# Grove_-_3-Axis_Digital_Accelerometer_400.net
KiCad netlist of a schematic drawn in EAGLE
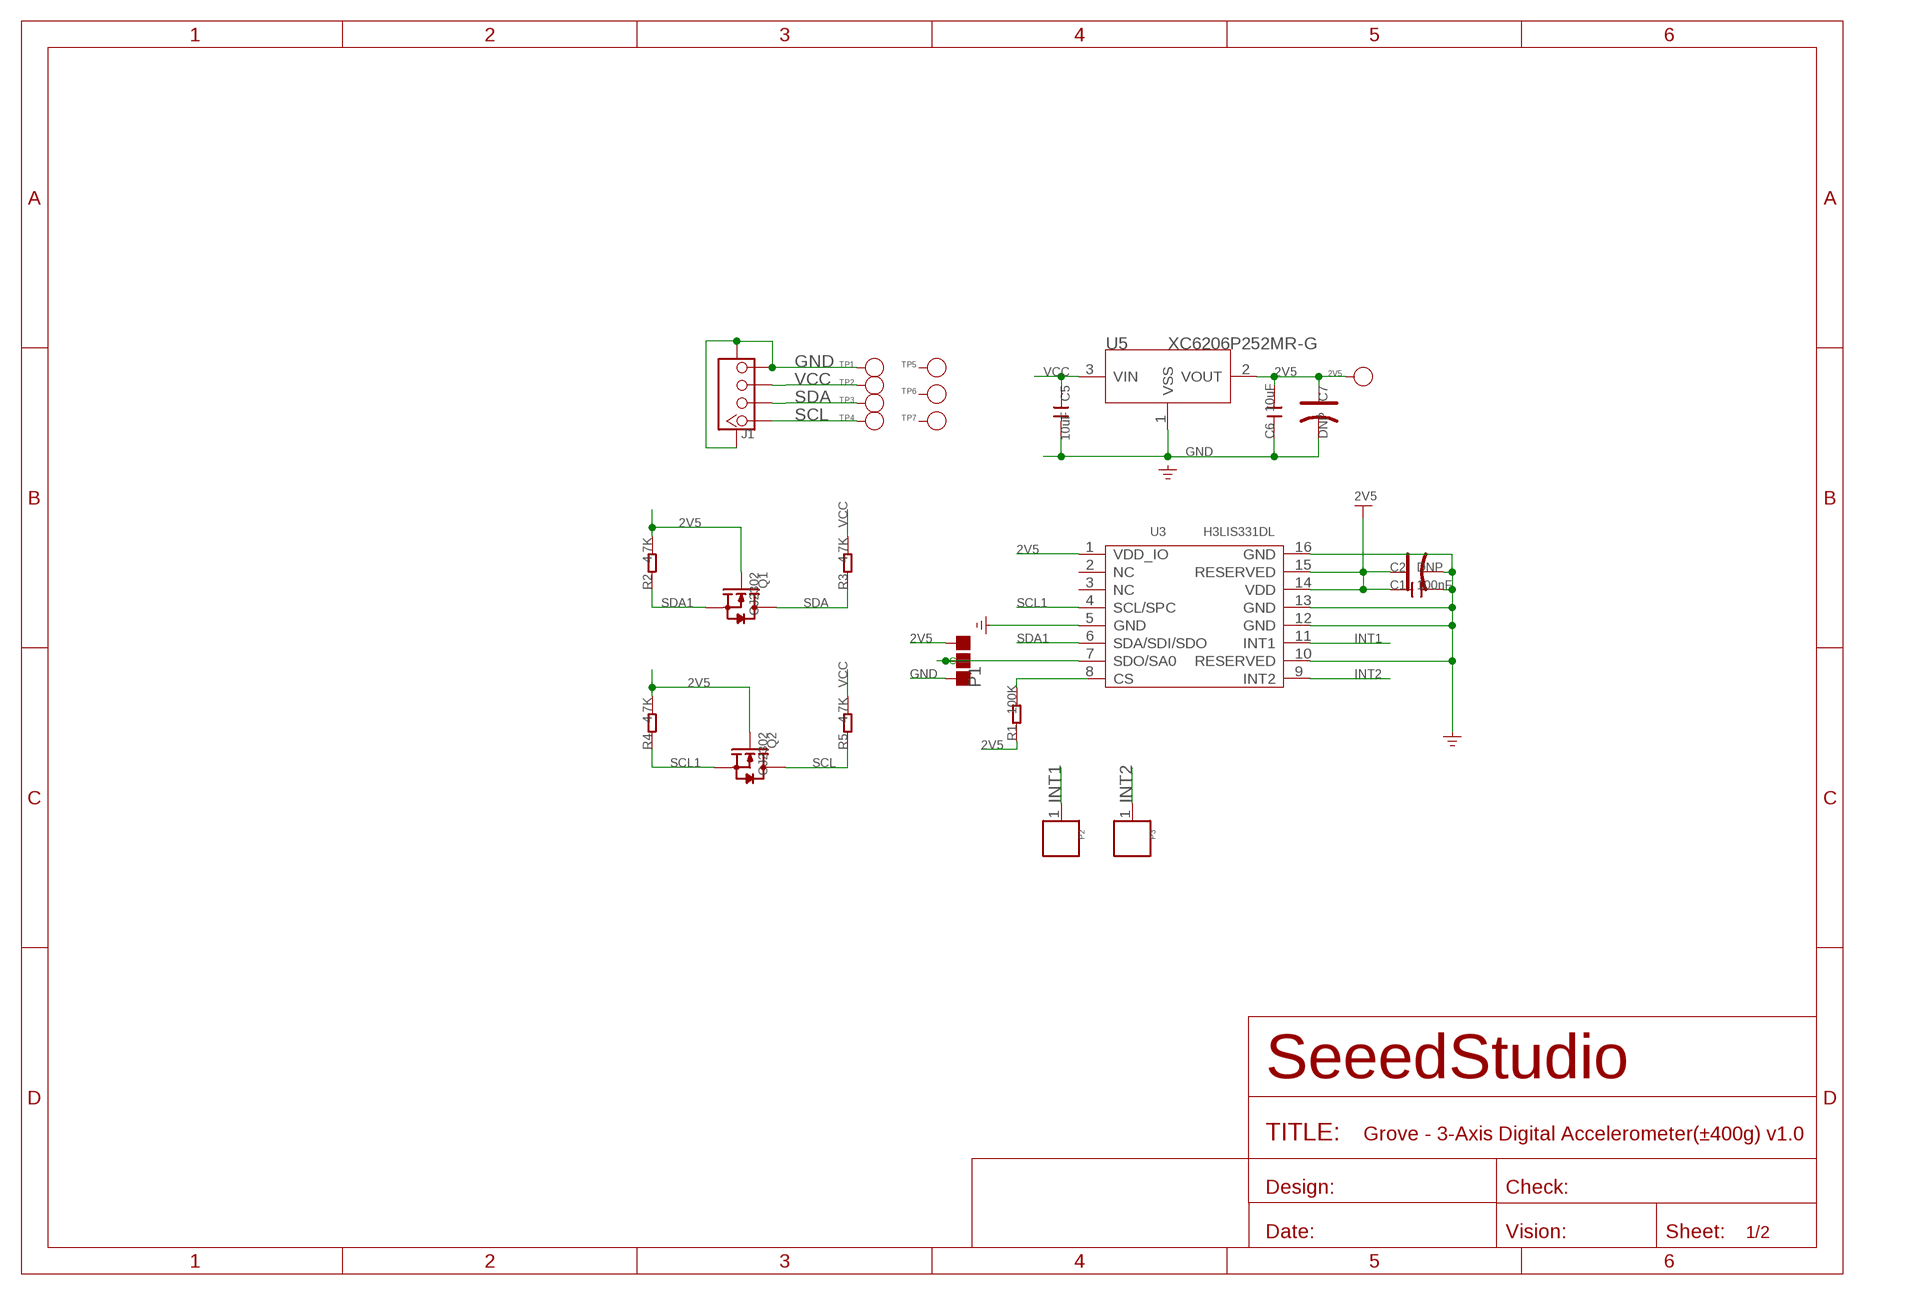
[diagram p0: schematic, sheet 1]
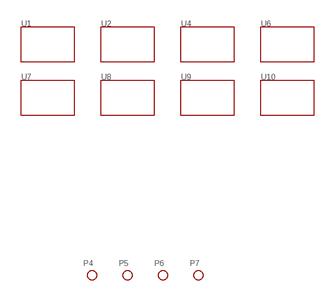
[diagram p1: schematic, sheet 2]

(export (version "E")
  (design (tool "Eeschema 10.0.6"))
  (components
    (comp (ref "2V5")
      (value "PAD-TEST-POINT'4545'")
      (footprint "eagle-import:TP_4545")
      (fields (field (name "PARTNO") "DNP"))
      (libsource (lib "eagle-import") (part "PAD-TEST-POINT'4545'"))
    )
    (comp (ref "C1")
      (value "100nF")
      (footprint "eagle-import:C0603")
      (libsource (lib "eagle-import") (part "C-0603"))
    )
    (comp (ref "C2")
      (value "DNP")
      (footprint "eagle-import:AVX-A")
      (libsource (lib "eagle-import") (part "CAP-AVX-A"))
    )
    (comp (ref "C5")
      (value "10uF")
      (footprint "eagle-import:C0805")
      (libsource (lib "eagle-import") (part "C-0805"))
    )
    (comp (ref "C6")
      (value "10uF")
      (footprint "eagle-import:C0805")
      (libsource (lib "eagle-import") (part "C-0805"))
    )
    (comp (ref "C7")
      (value "DNP")
      (footprint "eagle-import:AVX-A")
      (libsource (lib "eagle-import") (part "CAP-AVX-A"))
    )
    (comp (ref "J1")
      (value "TWIG-4P-2.0-SMD-FEMALE-REINFORCE'DD'")
      (footprint "eagle-import:4P-SMD-2.0")
      (libsource (lib "eagle-import") (part "TWIG-4P-2.0-SMD-FEMALE-REINFORCE'DD'"))
    )
    (comp (ref "P1")
      (value "PAD-JUMPER-3P-40*40")
      (footprint "eagle-import:3P-SMD-4.1X1.5")
      (fields (field (name "PARTNO") "DNP"))
      (libsource (lib "eagle-import") (part "PAD-JUMPER-3P-4040"))
    )
    (comp (ref "P2")
      (value "PAD'60/30'")
      (footprint "eagle-import:1P-65_35MIL")
      (libsource (lib "eagle-import") (part "PAD'60/30'"))
    )
    (comp (ref "P3")
      (value "PAD'60/30'")
      (footprint "eagle-import:1P-65_35MIL")
      (libsource (lib "eagle-import") (part "PAD'60/30'"))
    )
    (comp (ref "Q1")
      (value "CJ2302")
      (footprint "eagle-import:SOT23")
      (libsource (lib "eagle-import") (part "MOSFET-N'SOT23'"))
    )
    (comp (ref "Q2")
      (value "CJ2302")
      (footprint "eagle-import:SOT23")
      (libsource (lib "eagle-import") (part "MOSFET-N'SOT23'"))
    )
    (comp (ref "R1")
      (value "100K")
      (footprint "eagle-import:R0603")
      (libsource (lib "eagle-import") (part "R-0603"))
    )
    (comp (ref "R2")
      (value "4.7K")
      (footprint "eagle-import:R0603")
      (libsource (lib "eagle-import") (part "R-0603"))
    )
    (comp (ref "R3")
      (value "4.7K")
      (footprint "eagle-import:R0603")
      (libsource (lib "eagle-import") (part "R-0603"))
    )
    (comp (ref "R4")
      (value "4.7K")
      (footprint "eagle-import:R0603")
      (libsource (lib "eagle-import") (part "R-0603"))
    )
    (comp (ref "R5")
      (value "4.7K")
      (footprint "eagle-import:R0603")
      (libsource (lib "eagle-import") (part "R-0603"))
    )
    (comp (ref "TP1")
      (value "PAD-TEST-POINT'4545'")
      (footprint "eagle-import:TP_4545")
      (fields (field (name "PARTNO") "DNP"))
      (libsource (lib "eagle-import") (part "PAD-TEST-POINT'4545'"))
    )
    (comp (ref "TP2")
      (value "PAD-TEST-POINT'4545'")
      (footprint "eagle-import:TP_4545")
      (fields (field (name "PARTNO") "DNP"))
      (libsource (lib "eagle-import") (part "PAD-TEST-POINT'4545'"))
    )
    (comp (ref "TP3")
      (value "PAD-TEST-POINT'4545'")
      (footprint "eagle-import:TP_4545")
      (fields (field (name "PARTNO") "DNP"))
      (libsource (lib "eagle-import") (part "PAD-TEST-POINT'4545'"))
    )
    (comp (ref "TP4")
      (value "PAD-TEST-POINT'4545'")
      (footprint "eagle-import:TP_4545")
      (fields (field (name "PARTNO") "DNP"))
      (libsource (lib "eagle-import") (part "PAD-TEST-POINT'4545'"))
    )
    (comp (ref "TP5")
      (value "PAD-TEST-POINT'4545'")
      (footprint "eagle-import:TP_4545")
      (fields (field (name "PARTNO") "DNP"))
      (libsource (lib "eagle-import") (part "PAD-TEST-POINT'4545'"))
    )
    (comp (ref "TP6")
      (value "PAD-TEST-POINT'4545'")
      (footprint "eagle-import:TP_4545")
      (fields (field (name "PARTNO") "DNP"))
      (libsource (lib "eagle-import") (part "PAD-TEST-POINT'4545'"))
    )
    (comp (ref "TP7")
      (value "PAD-TEST-POINT'4545'")
      (footprint "eagle-import:TP_4545")
      (fields (field (name "PARTNO") "DNP"))
      (libsource (lib "eagle-import") (part "PAD-TEST-POINT'4545'"))
    )
    (comp (ref "U3")
      (value "H3LIS331DL")
      (footprint "eagle-import:TFLGA-16")
      (libsource (lib "eagle-import") (part "H3LIS331DL"))
    )
    (comp (ref "U5")
      (value "XC6206P252MR-G")
      (footprint "eagle-import:SOT23")
      (libsource (lib "eagle-import") (part "XC6206MR"))
    )
    (comp (ref "P4")
      (value "PAD-MARK")
      (footprint "eagle-import:ROUND-MARK-1.0")
      (fields (field (name "PARTNO") "DNP"))
      (libsource (lib "eagle-import") (part "PAD-MARK"))
    )
    (comp (ref "P5")
      (value "PAD-MARK")
      (footprint "eagle-import:ROUND-MARK-1.0")
      (fields (field (name "PARTNO") "DNP"))
      (libsource (lib "eagle-import") (part "PAD-MARK"))
    )
    (comp (ref "P6")
      (value "PAD-MARK")
      (footprint "eagle-import:ROUND-MARK-1.0")
      (fields (field (name "PARTNO") "DNP"))
      (libsource (lib "eagle-import") (part "PAD-MARK"))
    )
    (comp (ref "P7")
      (value "PAD-MARK")
      (footprint "eagle-import:ROUND-MARK-1.0")
      (fields (field (name "PARTNO") "DNP"))
      (libsource (lib "eagle-import") (part "PAD-MARK"))
    )
    (comp (ref "U1")
      (value "TWIG'2U'")
      (footprint "eagle-import:GROVE-TEST-PLATFORM")
      (libsource (lib "eagle-import") (part "TWIG'2U'"))
    )
    (comp (ref "U2")
      (value "TWIG'2U'")
      (footprint "eagle-import:GROVE-TEST-PLATFORM")
      (libsource (lib "eagle-import") (part "TWIG'2U'"))
    )
    (comp (ref "U4")
      (value "TWIG'2U'")
      (footprint "eagle-import:GROVE-TEST-PLATFORM")
      (libsource (lib "eagle-import") (part "TWIG'2U'"))
    )
    (comp (ref "U6")
      (value "TWIG'2U'")
      (footprint "eagle-import:GROVE-TEST-PLATFORM")
      (libsource (lib "eagle-import") (part "TWIG'2U'"))
    )
    (comp (ref "U7")
      (value "TWIG'2U'")
      (footprint "eagle-import:GROVE-TEST-PLATFORM")
      (libsource (lib "eagle-import") (part "TWIG'2U'"))
    )
    (comp (ref "U8")
      (value "TWIG'2U'")
      (footprint "eagle-import:GROVE-TEST-PLATFORM")
      (libsource (lib "eagle-import") (part "TWIG'2U'"))
    )
    (comp (ref "U9")
      (value "TWIG'2U'")
      (footprint "eagle-import:GROVE-TEST-PLATFORM")
      (libsource (lib "eagle-import") (part "TWIG'2U'"))
    )
    (comp (ref "U10")
      (value "TWIG'2U'")
      (footprint "eagle-import:GROVE-TEST-PLATFORM")
      (libsource (lib "eagle-import") (part "TWIG'2U'"))
    )
  )
  (nets
    (net (code "1") (name "2V5") (class "Default")
      (node (ref "2V5") (pin "T") (pinfunction "T_T") (pintype "bidirectional"))
      (node (ref "C1") (pin "1") (pinfunction "1_1") (pintype "passive"))
      (node (ref "C2") (pin "+") (pinfunction "+_+") (pintype "passive"))
      (node (ref "C6") (pin "2") (pinfunction "2_2") (pintype "passive"))
      (node (ref "C7") (pin "+") (pinfunction "+_+") (pintype "passive"))
      (node (ref "P1") (pin "00") (pinfunction "L_00") (pintype "bidirectional"))
      (node (ref "Q1") (pin "1") (pinfunction "G_1") (pintype "passive"))
      (node (ref "Q2") (pin "1") (pinfunction "G_1") (pintype "passive"))
      (node (ref "R1") (pin "1") (pinfunction "1_1") (pintype "passive"))
      (node (ref "R2") (pin "2") (pinfunction "2_2") (pintype "passive"))
      (node (ref "R4") (pin "2") (pinfunction "2_2") (pintype "passive"))
      (node (ref "U3") (pin "1") (pinfunction "VDD_IO_1") (pintype "bidirectional"))
      (node (ref "U3") (pin "14") (pinfunction "VDD_14") (pintype "bidirectional"))
      (node (ref "U3") (pin "15") (pinfunction "RESERVED_15") (pintype "bidirectional"))
      (node (ref "U5") (pin "2") (pinfunction "VOUT_2") (pintype "output"))
    )
    (net (code "2") (name "GND") (class "Default")
      (node (ref "C1") (pin "2") (pinfunction "2_2") (pintype "passive"))
      (node (ref "C2") (pin "-") (pinfunction "-_-") (pintype "passive"))
      (node (ref "C5") (pin "2") (pinfunction "2_2") (pintype "passive"))
      (node (ref "C6") (pin "1") (pinfunction "1_1") (pintype "passive"))
      (node (ref "C7") (pin "-") (pinfunction "-_-") (pintype "passive"))
      (node (ref "J1") (pin "4") (pinfunction "4_4") (pintype "bidirectional"))
      (node (ref "J1") (pin "SS1") (pinfunction "SS1_SS1") (pintype "bidirectional"))
      (node (ref "J1") (pin "SS2") (pinfunction "SS2_SS2") (pintype "bidirectional"))
      (node (ref "P1") (pin "11") (pinfunction "R_11") (pintype "bidirectional"))
      (node (ref "TP1") (pin "T") (pinfunction "T_T") (pintype "bidirectional"))
      (node (ref "U3") (pin "10") (pinfunction "RESERVED_10") (pintype "bidirectional"))
      (node (ref "U3") (pin "12") (pinfunction "GND_12") (pintype "bidirectional"))
      (node (ref "U3") (pin "13") (pinfunction "GND_13") (pintype "bidirectional"))
      (node (ref "U3") (pin "16") (pinfunction "GND_16") (pintype "bidirectional"))
      (node (ref "U3") (pin "5") (pinfunction "GND_5") (pintype "bidirectional"))
      (node (ref "U5") (pin "1") (pinfunction "VSS_1") (pintype "power_in"))
    )
    (net (code "3") (name "INT1") (class "Default")
      (node (ref "P2") (pin "1") (pinfunction "P$1_1") (pintype "bidirectional"))
      (node (ref "U3") (pin "11") (pinfunction "INT1_11") (pintype "bidirectional"))
    )
    (net (code "4") (name "INT2") (class "Default")
      (node (ref "P3") (pin "1") (pinfunction "P$1_1") (pintype "bidirectional"))
      (node (ref "U3") (pin "9") (pinfunction "INT2_9") (pintype "bidirectional"))
    )
    (net (code "5") (name "Net-(P1-C)") (class "Default")
      (node (ref "P1") (pin "MM") (pinfunction "C_MM") (pintype "bidirectional"))
      (node (ref "U3") (pin "7") (pinfunction "SDO/SA0_7") (pintype "bidirectional"))
    )
    (net (code "6") (name "SCL") (class "Default")
      (node (ref "J1") (pin "1") (pinfunction "1_1") (pintype "bidirectional"))
      (node (ref "Q2") (pin "3") (pinfunction "D_3") (pintype "passive"))
      (node (ref "R5") (pin "1") (pinfunction "1_1") (pintype "passive"))
      (node (ref "TP4") (pin "T") (pinfunction "T_T") (pintype "bidirectional"))
    )
    (net (code "7") (name "SCL1") (class "Default")
      (node (ref "Q2") (pin "2") (pinfunction "S_2") (pintype "passive"))
      (node (ref "R4") (pin "1") (pinfunction "1_1") (pintype "passive"))
      (node (ref "U3") (pin "4") (pinfunction "SCL/SPC_4") (pintype "bidirectional"))
    )
    (net (code "8") (name "SDA") (class "Default")
      (node (ref "J1") (pin "2") (pinfunction "2_2") (pintype "bidirectional"))
      (node (ref "Q1") (pin "3") (pinfunction "D_3") (pintype "passive"))
      (node (ref "R3") (pin "1") (pinfunction "1_1") (pintype "passive"))
      (node (ref "TP3") (pin "T") (pinfunction "T_T") (pintype "bidirectional"))
    )
    (net (code "9") (name "SDA1") (class "Default")
      (node (ref "Q1") (pin "2") (pinfunction "S_2") (pintype "passive"))
      (node (ref "R2") (pin "1") (pinfunction "1_1") (pintype "passive"))
      (node (ref "U3") (pin "6") (pinfunction "SDA/SDI/SDO_6") (pintype "bidirectional"))
    )
    (net (code "10") (name "VCC") (class "Default")
      (node (ref "C5") (pin "1") (pinfunction "1_1") (pintype "passive"))
      (node (ref "J1") (pin "3") (pinfunction "3_3") (pintype "bidirectional"))
      (node (ref "R3") (pin "2") (pinfunction "2_2") (pintype "passive"))
      (node (ref "R5") (pin "2") (pinfunction "2_2") (pintype "passive"))
      (node (ref "TP2") (pin "T") (pinfunction "T_T") (pintype "bidirectional"))
      (node (ref "U5") (pin "3") (pinfunction "VIN_3") (pintype "input"))
    )
    (net (code "11") (name "unconnected-(R1-Pad2)") (class "Default")
      (node (ref "R1") (pin "2") (pinfunction "2_2") (pintype "passive"))
    )
    (net (code "12") (name "unconnected-(TP5-PadT)") (class "Default")
      (node (ref "TP5") (pin "T") (pinfunction "T_T") (pintype "bidirectional"))
    )
    (net (code "13") (name "unconnected-(TP6-PadT)") (class "Default")
      (node (ref "TP6") (pin "T") (pinfunction "T_T") (pintype "bidirectional"))
    )
    (net (code "14") (name "unconnected-(TP7-PadT)") (class "Default")
      (node (ref "TP7") (pin "T") (pinfunction "T_T") (pintype "bidirectional"))
    )
    (net (code "15") (name "unconnected-(U3-CS-Pad8)") (class "Default")
      (node (ref "U3") (pin "8") (pinfunction "CS_8") (pintype "bidirectional"))
    )
    (net (code "16") (name "unconnected-(U3-NC-Pad2)") (class "Default")
      (node (ref "U3") (pin "2") (pinfunction "NC_2") (pintype "bidirectional"))
    )
    (net (code "17") (name "unconnected-(U3-NC-Pad3)") (class "Default")
      (node (ref "U3") (pin "3") (pinfunction "NC_3") (pintype "bidirectional"))
    )
  )
)
